# boardv1_1.net
KiCad netlist of a schematic drawn in EAGLE
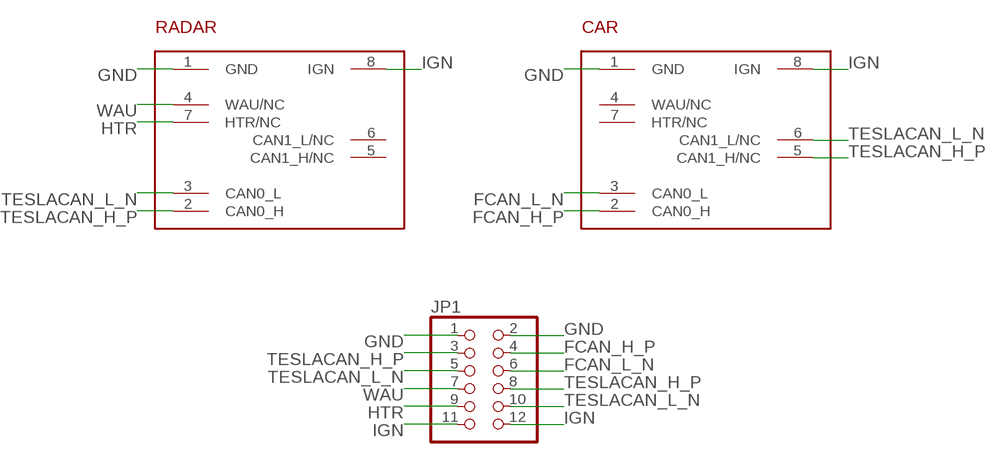
[diagram p0: schematic, sheet 1]

(export (version "E")
  (design (tool "Eeschema 10.0.6"))
  (components
    (comp (ref "CAR")
      (value "TE_AMP_1-967658-1")
      (footprint "eagle-import:TE_AMP_1-967658-1")
      (libsource (lib "eagle-import") (part "TE_AMP_1-967658-1"))
    )
    (comp (ref "JP1")
      (value "PINHD-2X6/90")
      (footprint "eagle-import:2X06_90")
      (libsource (lib "eagle-import") (part "PINHD-2X6/90"))
    )
    (comp (ref "RADAR")
      (value "TE_AMP_1-1534229-1TESLARADAR")
      (footprint "eagle-import:TE_AMP_1-1534229-1")
      (libsource (lib "eagle-import") (part "TE_AMP_1-1534229-1TESLARADAR"))
    )
  )
  (nets
    (net (code "1") (name "/FCAN_H_P") (class "Default")
      (node (ref "CAR") (pin "2") (pinfunction "CAN0_H_2") (pintype "bidirectional"))
      (node (ref "JP1") (pin "4") (pinfunction "4_4") (pintype "passive"))
    )
    (net (code "2") (name "/FCAN_L_N") (class "Default")
      (node (ref "CAR") (pin "3") (pinfunction "CAN0_L_3") (pintype "bidirectional"))
      (node (ref "JP1") (pin "6") (pinfunction "6_6") (pintype "passive"))
    )
    (net (code "3") (name "/GND") (class "Default")
      (node (ref "CAR") (pin "1") (pinfunction "GND_1") (pintype "power_in"))
      (node (ref "JP1") (pin "1") (pinfunction "1_1") (pintype "passive"))
      (node (ref "JP1") (pin "2") (pinfunction "2_2") (pintype "passive"))
      (node (ref "RADAR") (pin "1") (pinfunction "GND_1") (pintype "power_in"))
    )
    (net (code "4") (name "/HTR") (class "Default")
      (node (ref "JP1") (pin "9") (pinfunction "9_9") (pintype "passive"))
      (node (ref "RADAR") (pin "7") (pinfunction "HTR/NC_7") (pintype "bidirectional"))
    )
    (net (code "5") (name "/IGN") (class "Default")
      (node (ref "CAR") (pin "8") (pinfunction "IGN_8") (pintype "power_in"))
      (node (ref "JP1") (pin "11") (pinfunction "11_11") (pintype "passive"))
      (node (ref "JP1") (pin "12") (pinfunction "12_12") (pintype "passive"))
      (node (ref "RADAR") (pin "8") (pinfunction "IGN_8") (pintype "power_in"))
    )
    (net (code "6") (name "/TESLACAN_H_P") (class "Default")
      (node (ref "CAR") (pin "5") (pinfunction "CAN1_H/NC_5") (pintype "bidirectional"))
      (node (ref "JP1") (pin "3") (pinfunction "3_3") (pintype "passive"))
      (node (ref "JP1") (pin "8") (pinfunction "8_8") (pintype "passive"))
      (node (ref "RADAR") (pin "2") (pinfunction "CAN0_H_2") (pintype "bidirectional"))
    )
    (net (code "7") (name "/TESLACAN_L_N") (class "Default")
      (node (ref "CAR") (pin "6") (pinfunction "CAN1_L/NC_6") (pintype "bidirectional"))
      (node (ref "JP1") (pin "10") (pinfunction "10_10") (pintype "passive"))
      (node (ref "JP1") (pin "5") (pinfunction "5_5") (pintype "passive"))
      (node (ref "RADAR") (pin "3") (pinfunction "CAN0_L_3") (pintype "bidirectional"))
    )
    (net (code "8") (name "/WAU") (class "Default")
      (node (ref "JP1") (pin "7") (pinfunction "7_7") (pintype "passive"))
      (node (ref "RADAR") (pin "4") (pinfunction "WAU/NC_4") (pintype "bidirectional"))
    )
    (net (code "9") (name "unconnected-(CAR-HTR{slash}NC-Pad7)") (class "Default")
      (node (ref "CAR") (pin "7") (pinfunction "HTR/NC_7") (pintype "bidirectional"))
    )
    (net (code "10") (name "unconnected-(CAR-WAU{slash}NC-Pad4)") (class "Default")
      (node (ref "CAR") (pin "4") (pinfunction "WAU/NC_4") (pintype "bidirectional"))
    )
    (net (code "11") (name "unconnected-(RADAR-CAN1_H{slash}NC-Pad5)") (class "Default")
      (node (ref "RADAR") (pin "5") (pinfunction "CAN1_H/NC_5") (pintype "bidirectional"))
    )
    (net (code "12") (name "unconnected-(RADAR-CAN1_L{slash}NC-Pad6)") (class "Default")
      (node (ref "RADAR") (pin "6") (pinfunction "CAN1_L/NC_6") (pintype "bidirectional"))
    )
  )
)
